# Power_Muxing.net
KiCad netlist of a schematic drawn in Altium Designer
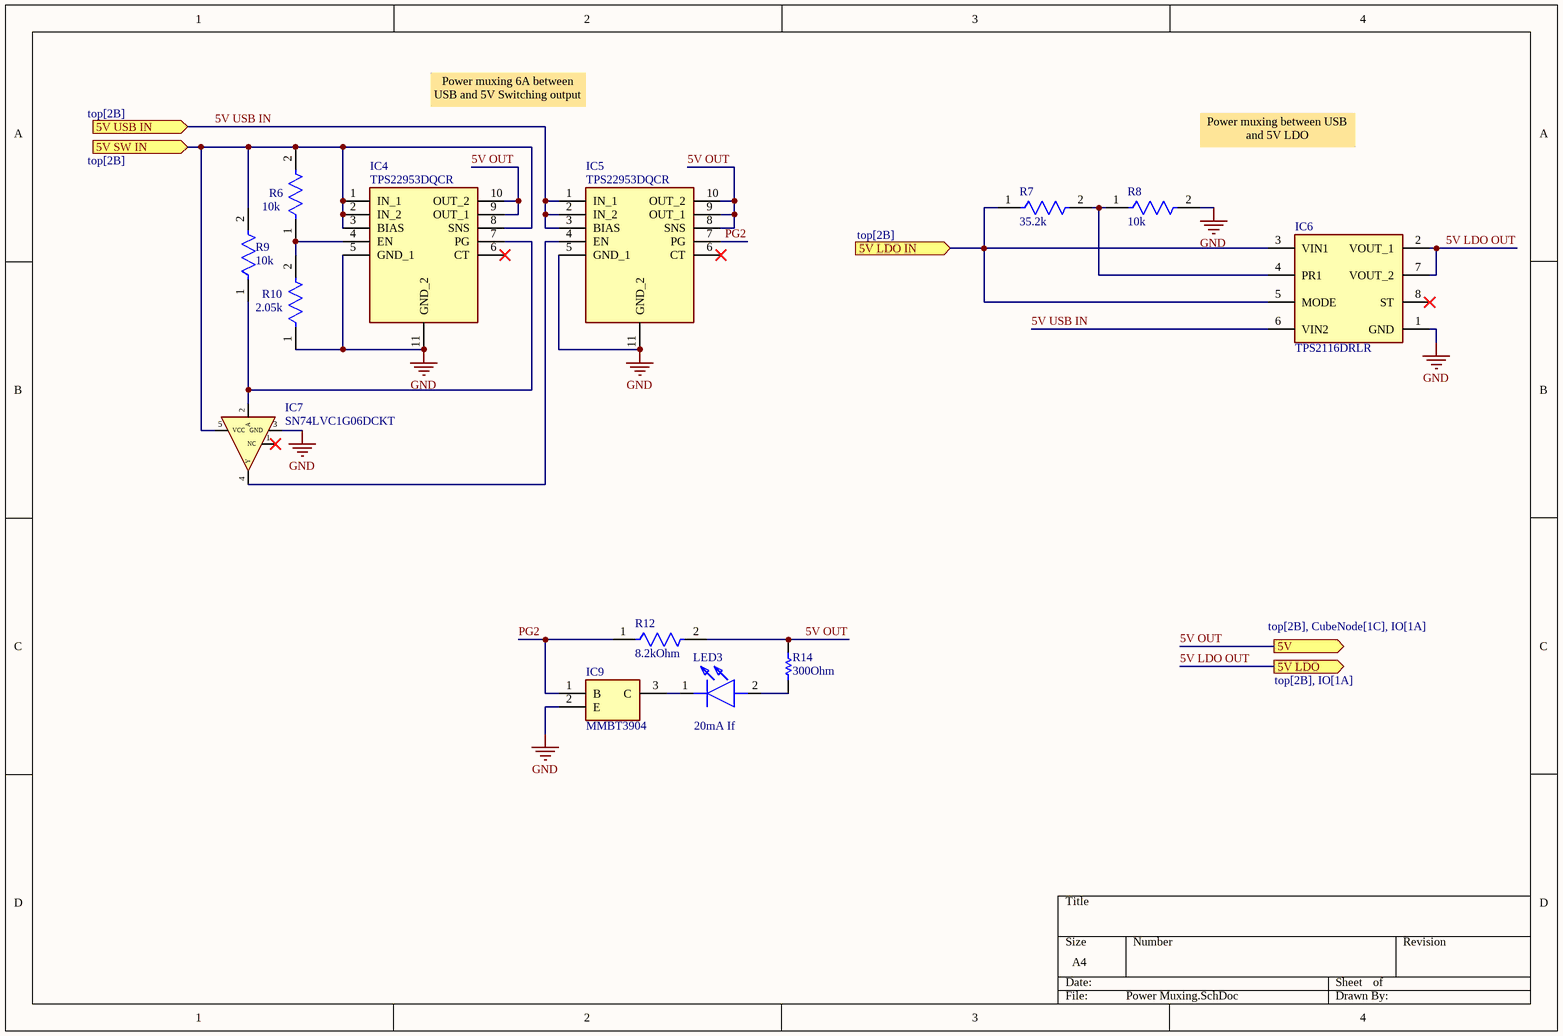
[diagram p0: Power Muxing.SchDoc]

(export (version "E")
  (design (tool "Eeschema 10.0.6"))
  (components
    (comp (ref "IC4")
      (value "TPS22953DQCR")
      (footprint "SamacSys:SON50P200X300X80-11N")
      (description "Integrated Circuit")
      (fields (field (name "MOUSER PART NUMBER") "595-TPS22953DQCR"))
      (libsource (lib "TPS22953DQCR") (part "TPS22953DQCR"))
    )
    (comp (ref "IC5")
      (value "TPS22953DQCR")
      (footprint "SamacSys:SON50P200X300X80-11N")
      (description "Integrated Circuit")
      (fields (field (name "MOUSER PART NUMBER") "595-TPS22953DQCR"))
      (libsource (lib "TPS22953DQCR") (part "TPS22953DQCR"))
    )
    (comp (ref "IC6")
      (value "TPS2116DRLR")
      (footprint "8PIN-SOT-5x3:8PIN-SOT-5x3")
      (description "d")
      (fields (field (name "MOUSER PART NUMBER") "595-TPS2116DRLR"))
      (libsource (lib "TPS2116") (part "TPS2116DRLR"))
    )
    (comp (ref "IC7")
      (value "SN74LVC1G06DCKT")
      (footprint "5PIN-SC70:5PIN-SC70")
      (description "Integrated Circuit")
      (fields (field (name "MOUSER PART NUMBER") "595-SN74LVC1G06DCKT"))
      (libsource (lib "SN74LVC1G06DCKT") (part "SN74LVC1G06DCKT"))
    )
    (comp (ref "IC9")
      (value "MMBT3904")
      (footprint "SamacSys:SOT95P240X120-3N")
      (description "Integrated Circuit")
      (fields (field (name "MOUSER PART NUMBER") "637-MMBT3904"))
      (libsource (lib "*") (part "MMBT3904"))
    )
    (comp (ref "LED3")
      (value "20mA If")
      (footprint "SamacSys:KGEELP4122PHRH35A8J820R18")
      (description "LED")
      (fields
        (field (name "MANUFACTURER_PART_NUMBER") "KG EELP41.22-PHRH-35-A8J8-20-R18")
        (field (name "MOUSER PART NUMBER") "720-P4122PHRH35A8J82")
      )
      (libsource (lib "*") (part "KG_EELP41.22-PHRH-35-A8J8-20-R18"))
    )
    (comp (ref "R6")
      (value "10k")
      (footprint "FP-AF0603-MFG")
      (description "Anti-Sulfurated Chip Resistors Automotive Grade 10kΩ 1% 100ppm/°C 0603")
      (libsource (lib "Altium Content Vault") (part "1029c3af85768c4190bb7ad29bc67b5"))
    )
    (comp (ref "R7")
      (value "35.2k")
      (footprint "YAGEO_GEN_PASSIVE:FP-RC0603-0_55-IPC_A")
      (description "High Precision-High Stability Chip Resistor Thin Film 0603 35.2kOhm 0.1% Paper T/R")
      (fields
        (field (name "MANUFACTURER") "Yageo")
        (field (name "MANUFACTURER PART NUMBER") "RT0603BRD0735K2L")
      )
      (libsource (lib "RT0603BRD0735K2L") (part "RT0603BRD0735K2L"))
    )
    (comp (ref "R8")
      (value "10k")
      (footprint "FP-RC0603-0_55-IPC_C")
      (description "RES 10K OHM 1% 1/10W 0603")
      (fields (field (name "TOLERANCE") "1%"))
      (libsource (lib "Altium Content Vault") (part "1029c3af85768c4190bb7ad29bc67b5"))
    )
    (comp (ref "R9")
      (value "10k")
      (footprint "FP-AF0603-MFG")
      (description "Anti-Sulfurated Chip Resistors Automotive Grade 10kΩ 1% 100ppm/°C 0603")
      (libsource (lib "Altium Content Vault") (part "1029c3af85768c4190bb7ad29bc67b5"))
    )
    (comp (ref "R10")
      (value "2.05k")
      (footprint "FP-AF0603-MFG")
      (description "Anti-Sulfurated Chip Resistors Automotive Grade 2.05kΩ 1% 100ppm/°C 0603")
      (fields (field (name "TOLERANCE") "1%"))
      (libsource (lib "Altium Content Vault") (part "1029c3af85768c4190bb7ad29bc67b5"))
    )
    (comp (ref "R12")
      (value "8.2kOhm")
      (footprint "FP-RC0603-0_55-MFG")
      (fields (field (name "TOLERANCE") "1%"))
      (libsource (lib "Altium Content Vault") (part "1029c3af85768c4190bb7ad29bc67b5"))
    )
    (comp (ref "R14")
      (value "300Ohm")
      (footprint "RESC1608X55X30LL20T20")
      (fields (field (name "PART NUMBER") "ERA3AEB301V") (field (name "MANUFACTURER") "Panasonic"))
      (libsource (lib "Altium Content Vault") (part "RES"))
    )
  )
  (nets
    (net (code "1") (name "/5V LDO IN") (class "Default")
      (node (ref "IC6") (pin "3") (pinfunction "VIN1_3") (pintype "passive"))
      (node (ref "IC6") (pin "5") (pinfunction "MODE_5") (pintype "passive"))
      (node (ref "R7") (pin "1") (pinfunction "1_1") (pintype "passive"))
    )
    (net (code "2") (name "/5V LDO OUT") (class "Default")
      (node (ref "IC6") (pin "2") (pinfunction "VOUT_1_2") (pintype "passive"))
      (node (ref "IC6") (pin "7") (pinfunction "VOUT_2_7") (pintype "passive"))
    )
    (net (code "3") (name "/5V OUT") (class "Default")
      (node (ref "IC4") (pin "10") (pinfunction "OUT_2_10") (pintype "passive"))
      (node (ref "IC4") (pin "9") (pinfunction "OUT_1_9") (pintype "passive"))
      (node (ref "IC5") (pin "10") (pinfunction "OUT_2_10") (pintype "passive"))
      (node (ref "IC5") (pin "8") (pinfunction "SNS_8") (pintype "passive"))
      (node (ref "IC5") (pin "9") (pinfunction "OUT_1_9") (pintype "passive"))
      (node (ref "R12") (pin "2") (pinfunction "2_2") (pintype "passive"))
      (node (ref "R14") (pin "2") (pinfunction "2_2") (pintype "passive"))
    )
    (net (code "4") (name "/5V SW IN") (class "Default")
      (node (ref "IC4") (pin "1") (pinfunction "IN_1_1") (pintype "passive"))
      (node (ref "IC4") (pin "2") (pinfunction "IN_2_2") (pintype "passive"))
      (node (ref "IC4") (pin "3") (pinfunction "BIAS_3") (pintype "passive"))
      (node (ref "IC4") (pin "8") (pinfunction "SNS_8") (pintype "passive"))
      (node (ref "IC7") (pin "5") (pinfunction "VCC_5") (pintype "passive"))
      (node (ref "R6") (pin "2") (pinfunction "2_2") (pintype "passive"))
      (node (ref "R9") (pin "2") (pinfunction "2_2") (pintype "passive"))
    )
    (net (code "5") (name "/5V USB IN") (class "Default")
      (node (ref "IC5") (pin "1") (pinfunction "IN_1_1") (pintype "passive"))
      (node (ref "IC5") (pin "2") (pinfunction "IN_2_2") (pintype "passive"))
      (node (ref "IC5") (pin "3") (pinfunction "BIAS_3") (pintype "passive"))
      (node (ref "IC6") (pin "6") (pinfunction "VIN2_6") (pintype "passive"))
    )
    (net (code "6") (name "/PG2") (class "Default")
      (node (ref "IC5") (pin "7") (pinfunction "PG_7") (pintype "passive"))
      (node (ref "IC9") (pin "1") (pinfunction "B_1") (pintype "passive"))
      (node (ref "R12") (pin "1") (pinfunction "1_1") (pintype "passive"))
    )
    (net (code "7") (name "GND") (class "Default")
      (node (ref "IC4") (pin "11") (pinfunction "GND_2_11") (pintype "passive"))
      (node (ref "IC4") (pin "5") (pinfunction "GND_1_5") (pintype "passive"))
      (node (ref "IC5") (pin "11") (pinfunction "GND_2_11") (pintype "passive"))
      (node (ref "IC5") (pin "5") (pinfunction "GND_1_5") (pintype "passive"))
      (node (ref "IC6") (pin "1") (pinfunction "GND_1") (pintype "passive"))
      (node (ref "IC7") (pin "3") (pinfunction "GND_3") (pintype "passive"))
      (node (ref "IC9") (pin "2") (pinfunction "E_2") (pintype "passive"))
      (node (ref "R10") (pin "1") (pinfunction "1_1") (pintype "passive"))
      (node (ref "R8") (pin "2") (pinfunction "2_2") (pintype "passive"))
    )
    (net (code "8") (name "Net-(IC4-EN)") (class "Default")
      (node (ref "IC4") (pin "4") (pinfunction "EN_4") (pintype "passive"))
      (node (ref "R10") (pin "2") (pinfunction "2_2") (pintype "passive"))
      (node (ref "R6") (pin "1") (pinfunction "1_1") (pintype "passive"))
    )
    (net (code "9") (name "Net-(IC4-PG)") (class "Default")
      (node (ref "IC4") (pin "7") (pinfunction "PG_7") (pintype "passive"))
      (node (ref "IC7") (pin "2") (pinfunction "A_2") (pintype "passive"))
      (node (ref "R9") (pin "1") (pinfunction "1_1") (pintype "passive"))
    )
    (net (code "10") (name "Net-(IC5-EN)") (class "Default")
      (node (ref "IC5") (pin "4") (pinfunction "EN_4") (pintype "passive"))
      (node (ref "IC7") (pin "4") (pinfunction "Y_4") (pintype "passive"))
    )
    (net (code "11") (name "Net-(IC6-PR1)") (class "Default")
      (node (ref "IC6") (pin "4") (pinfunction "PR1_4") (pintype "passive"))
      (node (ref "R7") (pin "2") (pinfunction "2_2") (pintype "passive"))
      (node (ref "R8") (pin "1") (pinfunction "1_1") (pintype "passive"))
    )
    (net (code "12") (name "Net-(IC9-C)") (class "Default")
      (node (ref "IC9") (pin "3") (pinfunction "C_3") (pintype "passive"))
      (node (ref "LED3") (pin "1") (pinfunction "K_1") (pintype "passive"))
    )
    (net (code "13") (name "Net-(LED3-A)") (class "Default")
      (node (ref "LED3") (pin "2") (pinfunction "A_2") (pintype "passive"))
      (node (ref "R14") (pin "1") (pinfunction "1_1") (pintype "passive"))
    )
    (net (code "14") (name "unconnected-(IC4-CT-Pad6)") (class "Default")
      (node (ref "IC4") (pin "6") (pinfunction "CT_6") (pintype "passive+no_connect"))
    )
    (net (code "15") (name "unconnected-(IC5-CT-Pad6)") (class "Default")
      (node (ref "IC5") (pin "6") (pinfunction "CT_6") (pintype "passive+no_connect"))
    )
    (net (code "16") (name "unconnected-(IC6-ST-Pad8)") (class "Default")
      (node (ref "IC6") (pin "8") (pinfunction "ST_8") (pintype "passive+no_connect"))
    )
    (net (code "17") (name "unconnected-(IC7-NC-Pad1)") (class "Default")
      (node (ref "IC7") (pin "1") (pinfunction "NC_1") (pintype "passive+no_connect"))
    )
  )
)
